# rs422.net
KiCad netlist of a schematic drawn in Altium Designer
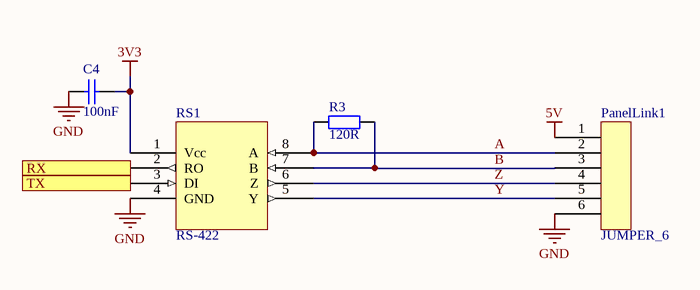
[diagram p0: rs422.SchDoc]

(export (version "E")
  (design (tool "Eeschema 10.0.6"))
  (components
    (comp (ref "C4")
      (value "100nF")
      (footprint "FP_0805_CAP_085")
      (description "Capacitor")
      (fields (field (name "TOLERANCE") "+80%/-20%") (field (name "VOLTAGE") "25V"))
      (libsource (lib "hallglib") (part "CAP 100nF"))
    )
    (comp (ref "PanelLink1")
      (value "JUMPER_6")
      (footprint "JUMPER_6")
      (libsource (lib "mylib") (part "JUMPER_6"))
    )
    (comp (ref "R3")
      (value "120R")
      (footprint "FP_0805_RES")
      (description "Resistor")
      (fields (field (name "TOLERANCE") "5%") (field (name "POWER") "125mW"))
      (libsource (lib "hallglib") (part "RES 120R"))
    )
    (comp (ref "RS1")
      (value "RS-422")
      (footprint "NSOIC-8")
      (description "RS-422 transceiver 3V3")
      (libsource (lib "mylib") (part "ISL83071"))
    )
  )
  (nets
    (net (code "1") (name "/A") (class "Default")
      (node (ref "PanelLink1") (pin "2") (pintype "passive"))
      (node (ref "R3") (pin "1") (pinfunction "1_1") (pintype "passive"))
      (node (ref "RS1") (pin "8") (pinfunction "A_8") (pintype "input"))
    )
    (net (code "2") (name "/B") (class "Default")
      (node (ref "PanelLink1") (pin "3") (pintype "passive"))
      (node (ref "R3") (pin "2") (pinfunction "2_2") (pintype "passive"))
      (node (ref "RS1") (pin "7") (pinfunction "B_7") (pintype "input"))
    )
    (net (code "3") (name "/RX") (class "Default")
      (node (ref "RS1") (pin "2") (pinfunction "RO_2") (pintype "output"))
    )
    (net (code "4") (name "/TX") (class "Default")
      (node (ref "RS1") (pin "3") (pinfunction "DI_3") (pintype "input"))
    )
    (net (code "5") (name "/Y") (class "Default")
      (node (ref "PanelLink1") (pin "5") (pintype "passive"))
      (node (ref "RS1") (pin "5") (pinfunction "Y_5") (pintype "output"))
    )
    (net (code "6") (name "/Z") (class "Default")
      (node (ref "PanelLink1") (pin "4") (pintype "passive"))
      (node (ref "RS1") (pin "6") (pinfunction "Z_6") (pintype "output"))
    )
    (net (code "7") (name "3V3") (class "Default")
      (node (ref "C4") (pin "1") (pinfunction "1_1") (pintype "passive"))
      (node (ref "RS1") (pin "1") (pinfunction "Vcc_1") (pintype "power_in"))
    )
    (net (code "8") (name "5V") (class "Default") (node (ref "PanelLink1") (pin "1") (pintype "passive")))
    (net (code "9") (name "GND") (class "Default")
      (node (ref "C4") (pin "2") (pinfunction "2_2") (pintype "passive"))
      (node (ref "PanelLink1") (pin "6") (pintype "passive"))
      (node (ref "RS1") (pin "4") (pinfunction "GND_4") (pintype "power_in"))
    )
  )
)
